# I2C_MUX.net
KiCad netlist of a schematic drawn in Altium Designer
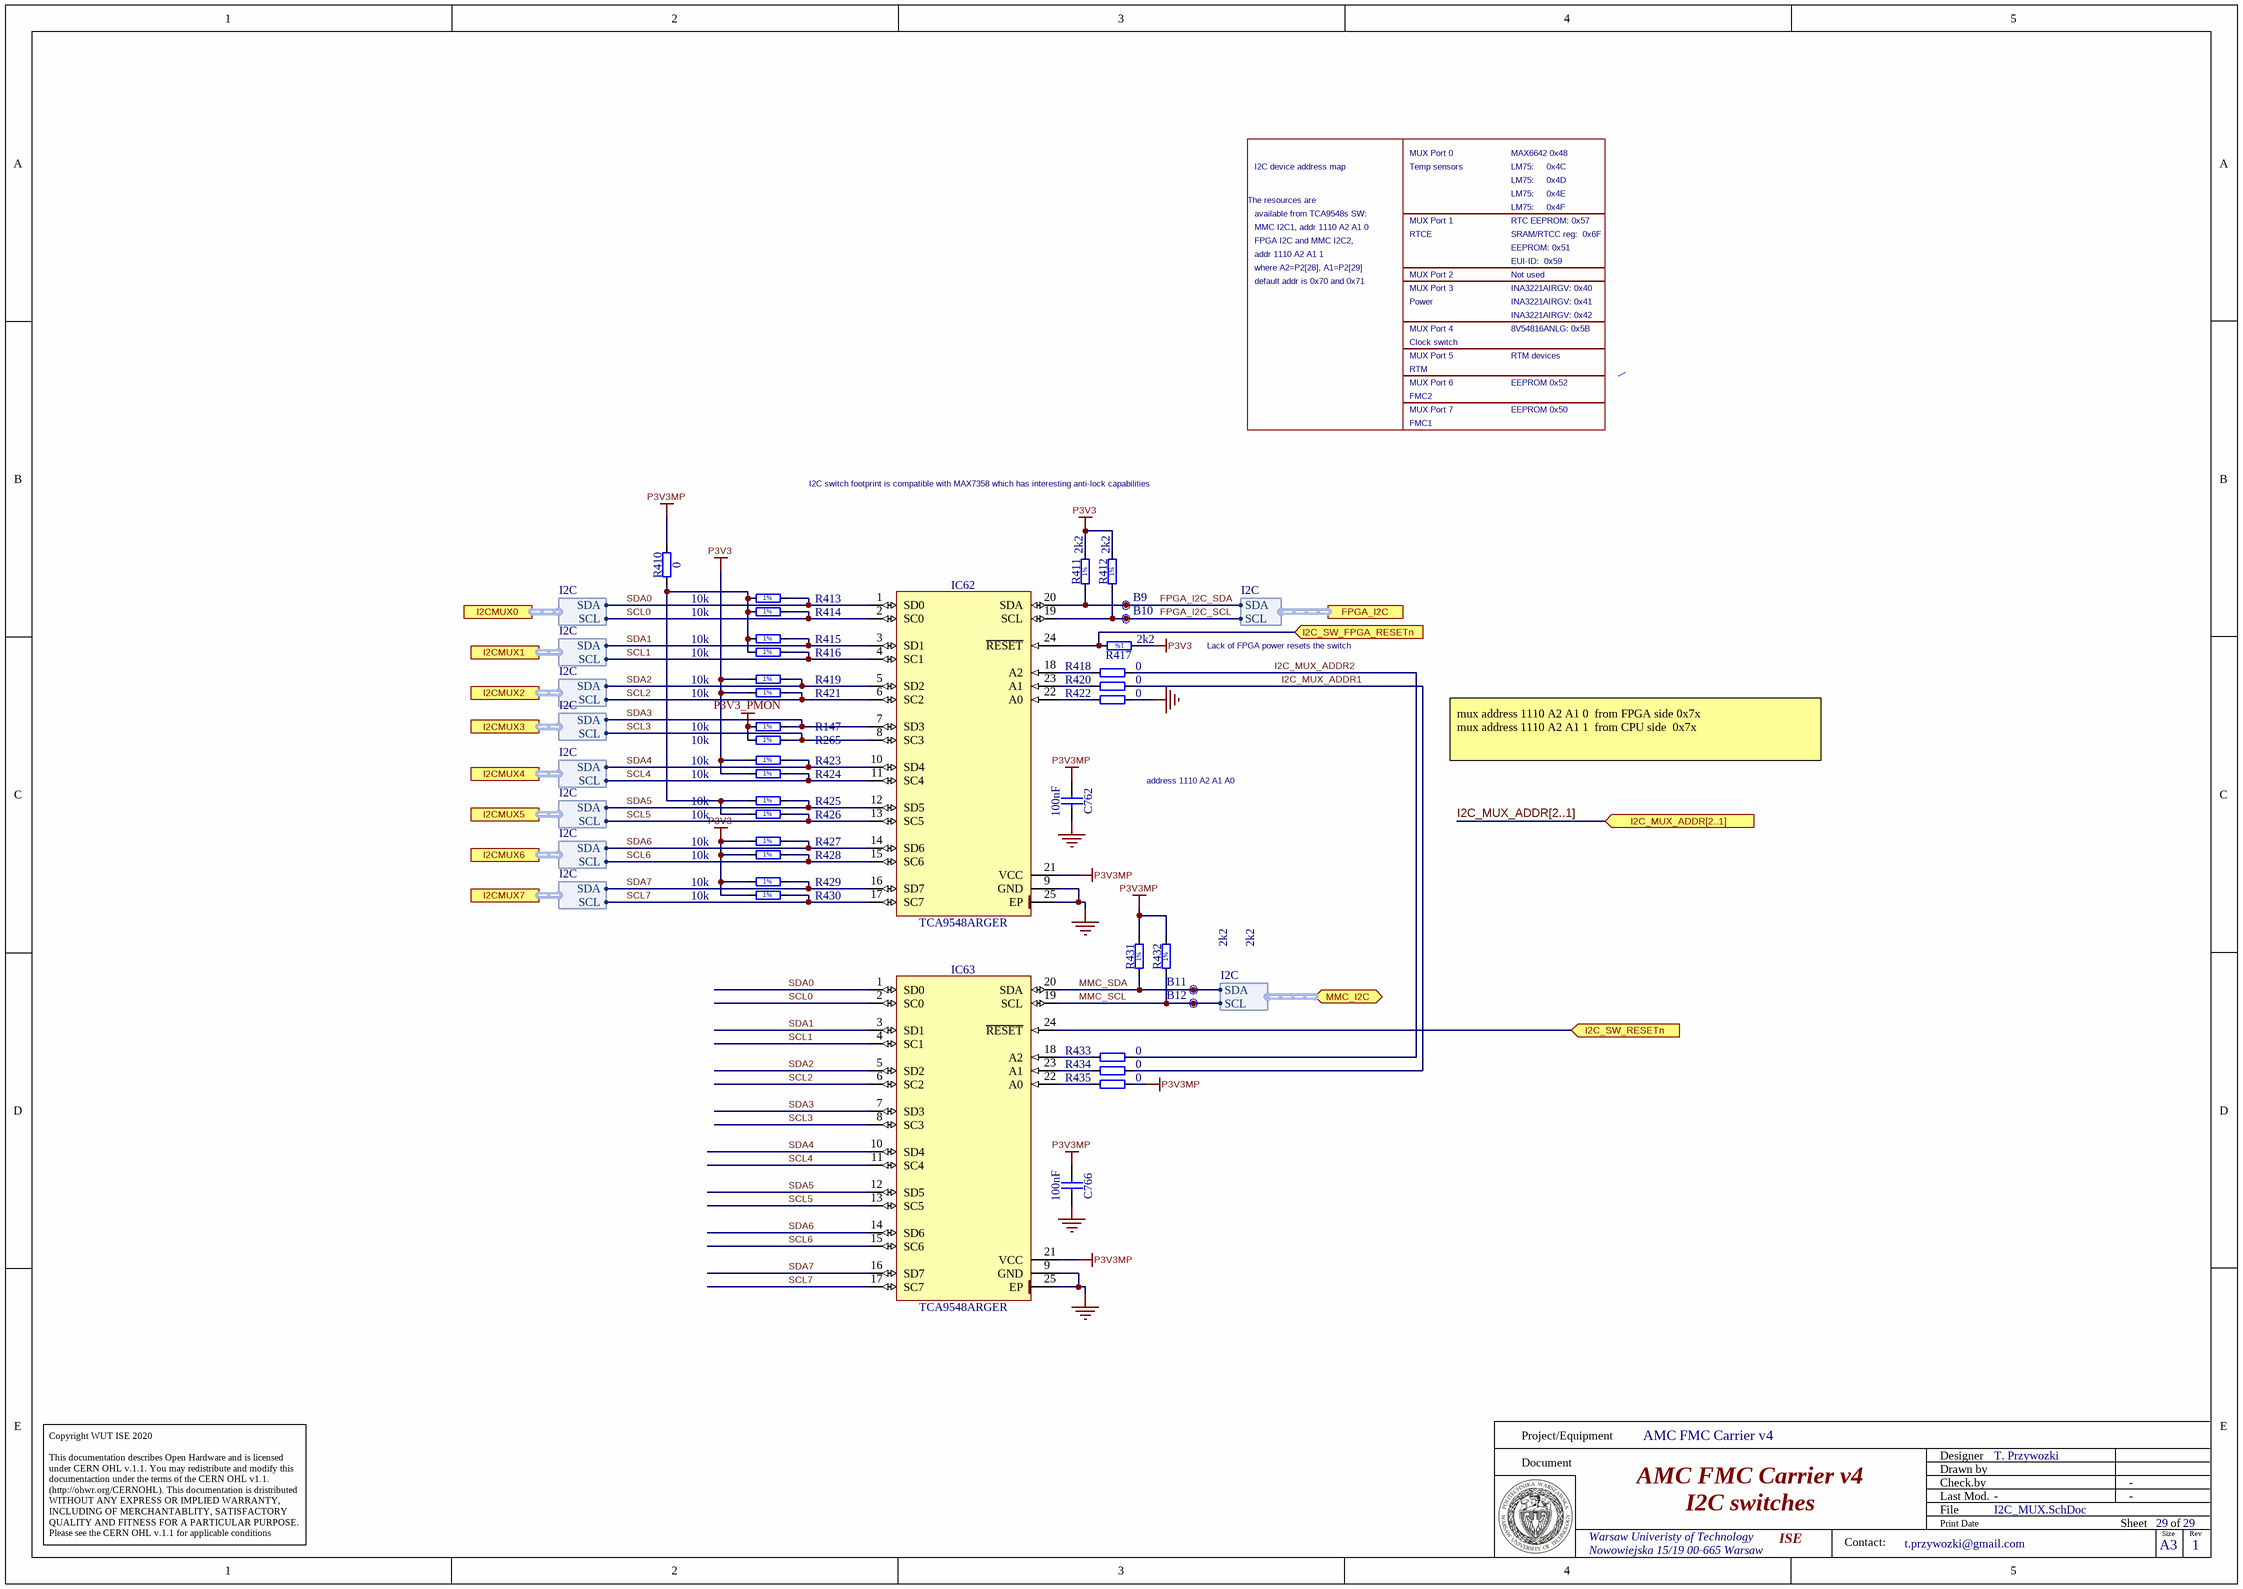
[diagram p0: I2C_MUX.SchDoc]

(export (version "E")
  (design (tool "Eeschema 10.0.6"))
  (components
    (comp (ref "B9")
      (value "SMD_PAD_D1MM")
      (footprint "C100")
      (libsource (lib "altium-import") (part "root_0__*"))
    )
    (comp (ref "B10")
      (value "SMD_PAD_D1MM")
      (footprint "C100")
      (libsource (lib "altium-import") (part "root_0__*"))
    )
    (comp (ref "B11")
      (value "SMD_PAD_D1MM")
      (footprint "C100")
      (libsource (lib "altium-import") (part "root_0__*"))
    )
    (comp (ref "B12")
      (value "SMD_PAD_D1MM")
      (footprint "C100")
      (libsource (lib "altium-import") (part "root_0__*"))
    )
    (comp (ref "C762")
      (value "100nF")
      (footprint "CAPC0603X33N")
      (description "Non-polarised capacitor")
      (fields
        (field (name "MANUFACTURER PART NUMBER") "CC0201_100NF_6.3V_10%_X5R")
        (field (name "MANUFACTURER") "GENERIC")
        (field (name "AUTHOR") "CERN DEM JLC")
      )
      (libsource (lib "Capacitors") (part "Capacitor - non polarized"))
    )
    (comp (ref "C766")
      (value "100nF")
      (footprint "CAPC0603X33N")
      (description "Non-polarised capacitor")
      (fields
        (field (name "MANUFACTURER PART NUMBER") "CC0201_100NF_6.3V_10%_X5R")
        (field (name "MANUFACTURER") "GENERIC")
        (field (name "AUTHOR") "CERN DEM JLC")
      )
      (libsource (lib "Capacitors") (part "Capacitor - non polarized"))
    )
    (comp (ref "IC62")
      (value "TCA9548ARGER")
      (footprint "QFN50P400X400X100-25N-S220")
      (description "Low Voltage 8-Channel I2C Switch With Reset")
      (fields (field (name "MANUFACTURER") "TEXAS INSTRUMENTS") (field (name "AUTHOR") "CERN DEM JLC"))
      (libsource (lib "ICs And Semiconductors") (part "TCA9548ARGER"))
    )
    (comp (ref "IC63")
      (value "TCA9548ARGER")
      (footprint "QFN50P400X400X100-25N-S220")
      (description "Low Voltage 8-Channel I2C Switch With Reset")
      (fields (field (name "MANUFACTURER") "TEXAS INSTRUMENTS") (field (name "AUTHOR") "CERN DEM JLC"))
      (libsource (lib "ICs And Semiconductors") (part "TCA9548ARGER"))
    )
    (comp (ref "R147")
      (value "10k")
      (footprint "RESC1005X40N")
      (description "Resistor - 1%")
      (fields
        (field (name "MANUFACTURER PART NUMBER") "R0402_10K_1%_0.0625W_100PPM")
        (field (name "MANUFACTURER") "GENERIC")
        (field (name "AUTHOR") "CERN DEM JLC")
      )
      (libsource (lib "Resistors") (part "Resistor - 1%"))
    )
    (comp (ref "R265")
      (value "10k")
      (footprint "RESC1005X40N")
      (description "Resistor - 1%")
      (fields
        (field (name "MANUFACTURER PART NUMBER") "R0402_10K_1%_0.0625W_100PPM")
        (field (name "MANUFACTURER") "GENERIC")
        (field (name "AUTHOR") "CERN DEM JLC")
      )
      (libsource (lib "Resistors") (part "Resistor - 1%"))
    )
    (comp (ref "R410")
      (value "0")
      (footprint "RESC1005X40N")
      (description "Resistor")
      (fields
        (field (name "MANUFACTURER PART NUMBER") "R0402_0R_JUMPER")
        (field (name "MANUFACTURER") "GENERIC")
        (field (name "AUTHOR") "CERN DEM JLC")
      )
      (libsource (lib "Resistors") (part "Resistor"))
    )
    (comp (ref "R411")
      (value "2k2")
      (footprint "RESC1005X40N")
      (description "Resistor - 1%")
      (fields
        (field (name "MANUFACTURER PART NUMBER") "R0402_2K2_1%_0.0625W_100PPM")
        (field (name "MANUFACTURER") "GENERIC")
        (field (name "AUTHOR") "CERN DEM JLC")
      )
      (libsource (lib "Resistors") (part "Resistor - 1%"))
    )
    (comp (ref "R412")
      (value "2k2")
      (footprint "RESC1005X40N")
      (description "Resistor - 1%")
      (fields
        (field (name "MANUFACTURER PART NUMBER") "R0402_2K2_1%_0.0625W_100PPM")
        (field (name "MANUFACTURER") "GENERIC")
        (field (name "AUTHOR") "CERN DEM JLC")
      )
      (libsource (lib "Resistors") (part "Resistor - 1%"))
    )
    (comp (ref "R413")
      (value "10k")
      (footprint "RESC1005X40N")
      (description "Resistor - 1%")
      (fields
        (field (name "MANUFACTURER PART NUMBER") "R0402_10K_1%_0.0625W_100PPM")
        (field (name "MANUFACTURER") "GENERIC")
        (field (name "AUTHOR") "CERN DEM JLC")
      )
      (libsource (lib "Resistors") (part "Resistor - 1%"))
    )
    (comp (ref "R414")
      (value "10k")
      (footprint "RESC1005X40N")
      (description "Resistor - 1%")
      (fields
        (field (name "MANUFACTURER PART NUMBER") "R0402_10K_1%_0.0625W_100PPM")
        (field (name "MANUFACTURER") "GENERIC")
        (field (name "AUTHOR") "CERN DEM JLC")
      )
      (libsource (lib "Resistors") (part "Resistor - 1%"))
    )
    (comp (ref "R415")
      (value "10k")
      (footprint "RESC1005X40N")
      (description "Resistor - 1%")
      (fields
        (field (name "MANUFACTURER PART NUMBER") "R0402_10K_1%_0.0625W_100PPM")
        (field (name "MANUFACTURER") "GENERIC")
        (field (name "AUTHOR") "CERN DEM JLC")
      )
      (libsource (lib "Resistors") (part "Resistor - 1%"))
    )
    (comp (ref "R416")
      (value "10k")
      (footprint "RESC1005X40N")
      (description "Resistor - 1%")
      (fields
        (field (name "MANUFACTURER PART NUMBER") "R0402_10K_1%_0.0625W_100PPM")
        (field (name "MANUFACTURER") "GENERIC")
        (field (name "AUTHOR") "CERN DEM JLC")
      )
      (libsource (lib "Resistors") (part "Resistor - 1%"))
    )
    (comp (ref "R417")
      (value "2k2")
      (footprint "RESC1005X40N")
      (description "Resistor - 1%")
      (fields
        (field (name "MANUFACTURER PART NUMBER") "R0402_2K2_1%_0.0625W_100PPM")
        (field (name "MANUFACTURER") "GENERIC")
        (field (name "AUTHOR") "CERN DEM JLC")
      )
      (libsource (lib "Resistors") (part "Resistor - 1%"))
    )
    (comp (ref "R418")
      (value "0")
      (footprint "RESC1005X40N")
      (description "Resistor")
      (fields
        (field (name "MANUFACTURER PART NUMBER") "R0402_0R_JUMPER")
        (field (name "MANUFACTURER") "GENERIC")
        (field (name "AUTHOR") "CERN DEM JLC")
      )
      (libsource (lib "Resistors") (part "Resistor"))
    )
    (comp (ref "R419")
      (value "10k")
      (footprint "RESC1005X40N")
      (description "Resistor - 1%")
      (fields
        (field (name "MANUFACTURER PART NUMBER") "R0402_10K_1%_0.0625W_100PPM")
        (field (name "MANUFACTURER") "GENERIC")
        (field (name "AUTHOR") "CERN DEM JLC")
      )
      (libsource (lib "Resistors") (part "Resistor - 1%"))
    )
    (comp (ref "R420")
      (value "0")
      (footprint "RESC1005X40N")
      (description "Resistor")
      (fields
        (field (name "MANUFACTURER PART NUMBER") "R0402_0R_JUMPER")
        (field (name "MANUFACTURER") "GENERIC")
        (field (name "AUTHOR") "CERN DEM JLC")
      )
      (libsource (lib "Resistors") (part "Resistor"))
    )
    (comp (ref "R421")
      (value "10k")
      (footprint "RESC1005X40N")
      (description "Resistor - 1%")
      (fields
        (field (name "MANUFACTURER PART NUMBER") "R0402_10K_1%_0.0625W_100PPM")
        (field (name "MANUFACTURER") "GENERIC")
        (field (name "AUTHOR") "CERN DEM JLC")
      )
      (libsource (lib "Resistors") (part "Resistor - 1%"))
    )
    (comp (ref "R422")
      (value "0")
      (footprint "RESC1005X40N")
      (description "Resistor")
      (fields
        (field (name "MANUFACTURER PART NUMBER") "R0402_0R_JUMPER")
        (field (name "MANUFACTURER") "GENERIC")
        (field (name "AUTHOR") "CERN DEM JLC")
      )
      (libsource (lib "Resistors") (part "Resistor"))
    )
    (comp (ref "R423")
      (value "10k")
      (footprint "RESC1005X40N")
      (description "Resistor - 1%")
      (fields
        (field (name "MANUFACTURER PART NUMBER") "R0402_10K_1%_0.0625W_100PPM")
        (field (name "MANUFACTURER") "GENERIC")
        (field (name "AUTHOR") "CERN DEM JLC")
      )
      (libsource (lib "Resistors") (part "Resistor - 1%"))
    )
    (comp (ref "R424")
      (value "10k")
      (footprint "RESC1005X40N")
      (description "Resistor - 1%")
      (fields
        (field (name "MANUFACTURER PART NUMBER") "R0402_10K_1%_0.0625W_100PPM")
        (field (name "MANUFACTURER") "GENERIC")
        (field (name "AUTHOR") "CERN DEM JLC")
      )
      (libsource (lib "Resistors") (part "Resistor - 1%"))
    )
    (comp (ref "R425")
      (value "10k")
      (footprint "RESC1005X40N")
      (description "Resistor - 1%")
      (fields
        (field (name "MANUFACTURER PART NUMBER") "R0402_10K_1%_0.0625W_100PPM")
        (field (name "MANUFACTURER") "GENERIC")
        (field (name "AUTHOR") "CERN DEM JLC")
      )
      (libsource (lib "Resistors") (part "Resistor - 1%"))
    )
    (comp (ref "R426")
      (value "10k")
      (footprint "RESC1005X40N")
      (description "Resistor - 1%")
      (fields
        (field (name "MANUFACTURER PART NUMBER") "R0402_10K_1%_0.0625W_100PPM")
        (field (name "MANUFACTURER") "GENERIC")
        (field (name "AUTHOR") "CERN DEM JLC")
      )
      (libsource (lib "Resistors") (part "Resistor - 1%"))
    )
    (comp (ref "R427")
      (value "10k")
      (footprint "RESC1005X40N")
      (description "Resistor - 1%")
      (fields
        (field (name "MANUFACTURER PART NUMBER") "R0402_10K_1%_0.0625W_100PPM")
        (field (name "MANUFACTURER") "GENERIC")
        (field (name "AUTHOR") "CERN DEM JLC")
      )
      (libsource (lib "Resistors") (part "Resistor - 1%"))
    )
    (comp (ref "R428")
      (value "10k")
      (footprint "RESC1005X40N")
      (description "Resistor - 1%")
      (fields
        (field (name "MANUFACTURER PART NUMBER") "R0402_10K_1%_0.0625W_100PPM")
        (field (name "MANUFACTURER") "GENERIC")
        (field (name "AUTHOR") "CERN DEM JLC")
      )
      (libsource (lib "Resistors") (part "Resistor - 1%"))
    )
    (comp (ref "R429")
      (value "10k")
      (footprint "RESC1005X40N")
      (description "Resistor - 1%")
      (fields
        (field (name "MANUFACTURER PART NUMBER") "R0402_10K_1%_0.0625W_100PPM")
        (field (name "MANUFACTURER") "GENERIC")
        (field (name "AUTHOR") "CERN DEM JLC")
      )
      (libsource (lib "Resistors") (part "Resistor - 1%"))
    )
    (comp (ref "R430")
      (value "10k")
      (footprint "RESC1005X40N")
      (description "Resistor - 1%")
      (fields
        (field (name "MANUFACTURER PART NUMBER") "R0402_10K_1%_0.0625W_100PPM")
        (field (name "MANUFACTURER") "GENERIC")
        (field (name "AUTHOR") "CERN DEM JLC")
      )
      (libsource (lib "Resistors") (part "Resistor - 1%"))
    )
    (comp (ref "R431")
      (value "2k2")
      (footprint "RESC1005X40N")
      (description "Resistor - 1%")
      (fields
        (field (name "MANUFACTURER PART NUMBER") "R0402_2K2_1%_0.0625W_100PPM")
        (field (name "MANUFACTURER") "GENERIC")
        (field (name "AUTHOR") "CERN DEM JLC")
      )
      (libsource (lib "Resistors") (part "Resistor - 1%"))
    )
    (comp (ref "R432")
      (value "2k2")
      (footprint "RESC1005X40N")
      (description "Resistor - 1%")
      (fields
        (field (name "MANUFACTURER PART NUMBER") "R0402_2K2_1%_0.0625W_100PPM")
        (field (name "MANUFACTURER") "GENERIC")
        (field (name "AUTHOR") "CERN DEM JLC")
      )
      (libsource (lib "Resistors") (part "Resistor - 1%"))
    )
    (comp (ref "R433")
      (value "0")
      (footprint "RESC1005X40N")
      (description "Resistor")
      (fields
        (field (name "MANUFACTURER PART NUMBER") "R0402_0R_JUMPER")
        (field (name "MANUFACTURER") "GENERIC")
        (field (name "AUTHOR") "CERN DEM JLC")
      )
      (libsource (lib "Resistors") (part "Resistor"))
    )
    (comp (ref "R434")
      (value "0")
      (footprint "RESC1005X40N")
      (description "Resistor")
      (fields
        (field (name "MANUFACTURER PART NUMBER") "R0402_0R_JUMPER")
        (field (name "MANUFACTURER") "GENERIC")
        (field (name "AUTHOR") "CERN DEM JLC")
      )
      (libsource (lib "Resistors") (part "Resistor"))
    )
    (comp (ref "R435")
      (value "0")
      (footprint "RESC1005X40N")
      (description "Resistor")
      (fields
        (field (name "MANUFACTURER PART NUMBER") "R0402_0R_JUMPER")
        (field (name "MANUFACTURER") "GENERIC")
        (field (name "AUTHOR") "CERN DEM JLC")
      )
      (libsource (lib "Resistors") (part "Resistor"))
    )
  )
  (nets
    (net (code "2") (name "/FPGA_I2C_SCL") (class "Default")
      (node (ref "B10") (pin "1") (pinfunction "1_1") (pintype "passive"))
      (node (ref "IC62") (pin "19") (pinfunction "SCL_19") (pintype "bidirectional"))
      (node (ref "R412") (pin "1") (pinfunction "1_1") (pintype "passive"))
    )
    (net (code "3") (name "/FPGA_I2C_SDA") (class "Default")
      (node (ref "B9") (pin "1") (pinfunction "1_1") (pintype "passive"))
      (node (ref "IC62") (pin "20") (pinfunction "SDA_20") (pintype "bidirectional"))
      (node (ref "R411") (pin "1") (pinfunction "1_1") (pintype "passive"))
    )
    (net (code "4") (name "/I2C_MUX_ADDR1") (class "Default")
      (node (ref "R420") (pin "1") (pinfunction "1_1") (pintype "passive"))
      (node (ref "R434") (pin "1") (pinfunction "1_1") (pintype "passive"))
    )
    (net (code "5") (name "/I2C_MUX_ADDR2") (class "Default")
      (node (ref "R418") (pin "1") (pinfunction "1_1") (pintype "passive"))
      (node (ref "R433") (pin "1") (pinfunction "1_1") (pintype "passive"))
    )
    (net (code "7") (name "/I2C_SW_FPGA_RESETn") (class "Default")
      (node (ref "IC62") (pin "24") (pinfunction "~{RESET}_24") (pintype "input"))
      (node (ref "R417") (pin "2") (pinfunction "2_2") (pintype "passive"))
    )
    (net (code "8") (name "/I2C_SW_RESETn") (class "Default")
      (node (ref "IC63") (pin "24") (pinfunction "~{RESET}_24") (pintype "input"))
    )
    (net (code "9") (name "/MMC_SCL") (class "Default")
      (node (ref "B12") (pin "1") (pinfunction "1_1") (pintype "passive"))
      (node (ref "IC63") (pin "19") (pinfunction "SCL_19") (pintype "bidirectional"))
      (node (ref "R432") (pin "1") (pinfunction "1_1") (pintype "passive"))
    )
    (net (code "10") (name "/MMC_SDA") (class "Default")
      (node (ref "B11") (pin "1") (pinfunction "1_1") (pintype "passive"))
      (node (ref "IC63") (pin "20") (pinfunction "SDA_20") (pintype "bidirectional"))
      (node (ref "R431") (pin "1") (pinfunction "1_1") (pintype "passive"))
    )
    (net (code "11") (name "/SCL0") (class "Default")
      (node (ref "IC62") (pin "2") (pinfunction "SC0_2") (pintype "bidirectional"))
      (node (ref "IC63") (pin "2") (pinfunction "SC0_2") (pintype "bidirectional"))
      (node (ref "R414") (pin "2") (pinfunction "2_2") (pintype "passive"))
    )
    (net (code "12") (name "/SCL1") (class "Default")
      (node (ref "IC62") (pin "4") (pinfunction "SC1_4") (pintype "bidirectional"))
      (node (ref "IC63") (pin "4") (pinfunction "SC1_4") (pintype "bidirectional"))
      (node (ref "R416") (pin "2") (pinfunction "2_2") (pintype "passive"))
    )
    (net (code "13") (name "/SCL2") (class "Default")
      (node (ref "IC62") (pin "6") (pinfunction "SC2_6") (pintype "bidirectional"))
      (node (ref "IC63") (pin "6") (pinfunction "SC2_6") (pintype "bidirectional"))
      (node (ref "R421") (pin "2") (pinfunction "2_2") (pintype "passive"))
    )
    (net (code "14") (name "/SCL3") (class "Default")
      (node (ref "IC62") (pin "8") (pinfunction "SC3_8") (pintype "bidirectional"))
      (node (ref "IC63") (pin "8") (pinfunction "SC3_8") (pintype "bidirectional"))
      (node (ref "R265") (pin "2") (pinfunction "2_2") (pintype "passive"))
    )
    (net (code "15") (name "/SCL4") (class "Default")
      (node (ref "IC62") (pin "11") (pinfunction "SC4_11") (pintype "bidirectional"))
      (node (ref "IC63") (pin "11") (pinfunction "SC4_11") (pintype "bidirectional"))
      (node (ref "R424") (pin "2") (pinfunction "2_2") (pintype "passive"))
    )
    (net (code "16") (name "/SCL5") (class "Default")
      (node (ref "IC62") (pin "13") (pinfunction "SC5_13") (pintype "bidirectional"))
      (node (ref "IC63") (pin "13") (pinfunction "SC5_13") (pintype "bidirectional"))
      (node (ref "R426") (pin "2") (pinfunction "2_2") (pintype "passive"))
    )
    (net (code "17") (name "/SCL6") (class "Default")
      (node (ref "IC62") (pin "15") (pinfunction "SC6_15") (pintype "bidirectional"))
      (node (ref "IC63") (pin "15") (pinfunction "SC6_15") (pintype "bidirectional"))
      (node (ref "R428") (pin "2") (pinfunction "2_2") (pintype "passive"))
    )
    (net (code "18") (name "/SCL7") (class "Default")
      (node (ref "IC62") (pin "17") (pinfunction "SC7_17") (pintype "bidirectional"))
      (node (ref "IC63") (pin "17") (pinfunction "SC7_17") (pintype "bidirectional"))
      (node (ref "R430") (pin "2") (pinfunction "2_2") (pintype "passive"))
    )
    (net (code "19") (name "/SDA0") (class "Default")
      (node (ref "IC62") (pin "1") (pinfunction "SD0_1") (pintype "bidirectional"))
      (node (ref "IC63") (pin "1") (pinfunction "SD0_1") (pintype "bidirectional"))
      (node (ref "R413") (pin "2") (pinfunction "2_2") (pintype "passive"))
    )
    (net (code "20") (name "/SDA1") (class "Default")
      (node (ref "IC62") (pin "3") (pinfunction "SD1_3") (pintype "bidirectional"))
      (node (ref "IC63") (pin "3") (pinfunction "SD1_3") (pintype "bidirectional"))
      (node (ref "R415") (pin "2") (pinfunction "2_2") (pintype "passive"))
    )
    (net (code "21") (name "/SDA2") (class "Default")
      (node (ref "IC62") (pin "5") (pinfunction "SD2_5") (pintype "bidirectional"))
      (node (ref "IC63") (pin "5") (pinfunction "SD2_5") (pintype "bidirectional"))
      (node (ref "R419") (pin "2") (pinfunction "2_2") (pintype "passive"))
    )
    (net (code "22") (name "/SDA3") (class "Default")
      (node (ref "IC62") (pin "7") (pinfunction "SD3_7") (pintype "bidirectional"))
      (node (ref "IC63") (pin "7") (pinfunction "SD3_7") (pintype "bidirectional"))
      (node (ref "R147") (pin "2") (pinfunction "2_2") (pintype "passive"))
    )
    (net (code "23") (name "/SDA4") (class "Default")
      (node (ref "IC62") (pin "10") (pinfunction "SD4_10") (pintype "bidirectional"))
      (node (ref "IC63") (pin "10") (pinfunction "SD4_10") (pintype "bidirectional"))
      (node (ref "R423") (pin "2") (pinfunction "2_2") (pintype "passive"))
    )
    (net (code "24") (name "/SDA5") (class "Default")
      (node (ref "IC62") (pin "12") (pinfunction "SD5_12") (pintype "bidirectional"))
      (node (ref "IC63") (pin "12") (pinfunction "SD5_12") (pintype "bidirectional"))
      (node (ref "R425") (pin "2") (pinfunction "2_2") (pintype "passive"))
    )
    (net (code "25") (name "/SDA6") (class "Default")
      (node (ref "IC62") (pin "14") (pinfunction "SD6_14") (pintype "bidirectional"))
      (node (ref "IC63") (pin "14") (pinfunction "SD6_14") (pintype "bidirectional"))
      (node (ref "R427") (pin "2") (pinfunction "2_2") (pintype "passive"))
    )
    (net (code "26") (name "/SDA7") (class "Default")
      (node (ref "IC62") (pin "16") (pinfunction "SD7_16") (pintype "bidirectional"))
      (node (ref "IC63") (pin "16") (pinfunction "SD7_16") (pintype "bidirectional"))
      (node (ref "R429") (pin "2") (pinfunction "2_2") (pintype "passive"))
    )
    (net (code "28") (name "GND") (class "Default")
      (node (ref "C762") (pin "2") (pinfunction "2_2") (pintype "passive"))
      (node (ref "C766") (pin "2") (pinfunction "2_2") (pintype "passive"))
      (node (ref "IC62") (pin "25") (pinfunction "EP_25") (pintype "power_in"))
      (node (ref "IC62") (pin "9") (pinfunction "GND_9") (pintype "power_in"))
      (node (ref "IC63") (pin "25") (pinfunction "EP_25") (pintype "power_in"))
      (node (ref "IC63") (pin "9") (pinfunction "GND_9") (pintype "power_in"))
      (node (ref "R422") (pin "1") (pinfunction "1_1") (pintype "passive"))
    )
    (net (code "29") (name "Net-(IC62-A0)") (class "Default")
      (node (ref "IC62") (pin "22") (pinfunction "A0_22") (pintype "input"))
      (node (ref "R422") (pin "2") (pinfunction "2_2") (pintype "passive"))
    )
    (net (code "30") (name "Net-(IC62-A1)") (class "Default")
      (node (ref "IC62") (pin "23") (pinfunction "A1_23") (pintype "input"))
      (node (ref "R420") (pin "2") (pinfunction "2_2") (pintype "passive"))
    )
    (net (code "31") (name "Net-(IC62-A2)") (class "Default")
      (node (ref "IC62") (pin "18") (pinfunction "A2_18") (pintype "input"))
      (node (ref "R418") (pin "2") (pinfunction "2_2") (pintype "passive"))
    )
    (net (code "32") (name "Net-(IC63-A0)") (class "Default")
      (node (ref "IC63") (pin "22") (pinfunction "A0_22") (pintype "input"))
      (node (ref "R435") (pin "2") (pinfunction "2_2") (pintype "passive"))
    )
    (net (code "33") (name "Net-(IC63-A1)") (class "Default")
      (node (ref "IC63") (pin "23") (pinfunction "A1_23") (pintype "input"))
      (node (ref "R434") (pin "2") (pinfunction "2_2") (pintype "passive"))
    )
    (net (code "34") (name "Net-(IC63-A2)") (class "Default")
      (node (ref "IC63") (pin "18") (pinfunction "A2_18") (pintype "input"))
      (node (ref "R433") (pin "2") (pinfunction "2_2") (pintype "passive"))
    )
    (net (code "35") (name "Net-(R410-Pad2)") (class "Default")
      (node (ref "R410") (pin "2") (pinfunction "2_2") (pintype "passive"))
      (node (ref "R413") (pin "1") (pinfunction "1_1") (pintype "passive"))
      (node (ref "R414") (pin "1") (pinfunction "1_1") (pintype "passive"))
      (node (ref "R415") (pin "1") (pinfunction "1_1") (pintype "passive"))
      (node (ref "R416") (pin "1") (pinfunction "1_1") (pintype "passive"))
      (node (ref "R425") (pin "1") (pinfunction "1_1") (pintype "passive"))
      (node (ref "R426") (pin "1") (pinfunction "1_1") (pintype "passive"))
    )
    (net (code "36") (name "P3V3") (class "Default")
      (node (ref "R411") (pin "2") (pinfunction "2_2") (pintype "passive"))
      (node (ref "R412") (pin "2") (pinfunction "2_2") (pintype "passive"))
      (node (ref "R417") (pin "1") (pinfunction "1_1") (pintype "passive"))
      (node (ref "R419") (pin "1") (pinfunction "1_1") (pintype "passive"))
      (node (ref "R421") (pin "1") (pinfunction "1_1") (pintype "passive"))
      (node (ref "R423") (pin "1") (pinfunction "1_1") (pintype "passive"))
      (node (ref "R424") (pin "1") (pinfunction "1_1") (pintype "passive"))
      (node (ref "R427") (pin "1") (pinfunction "1_1") (pintype "passive"))
      (node (ref "R428") (pin "1") (pinfunction "1_1") (pintype "passive"))
      (node (ref "R429") (pin "1") (pinfunction "1_1") (pintype "passive"))
      (node (ref "R430") (pin "1") (pinfunction "1_1") (pintype "passive"))
    )
    (net (code "37") (name "P3V3MP") (class "Default")
      (node (ref "C762") (pin "1") (pinfunction "1_1") (pintype "passive"))
      (node (ref "C766") (pin "1") (pinfunction "1_1") (pintype "passive"))
      (node (ref "IC62") (pin "21") (pinfunction "VCC_21") (pintype "power_in"))
      (node (ref "IC63") (pin "21") (pinfunction "VCC_21") (pintype "power_in"))
      (node (ref "R410") (pin "1") (pinfunction "1_1") (pintype "passive"))
      (node (ref "R431") (pin "2") (pinfunction "2_2") (pintype "passive"))
      (node (ref "R432") (pin "2") (pinfunction "2_2") (pintype "passive"))
      (node (ref "R435") (pin "1") (pinfunction "1_1") (pintype "passive"))
    )
    (net (code "38") (name "P3V3_PMON") (class "Default")
      (node (ref "R147") (pin "1") (pinfunction "1_1") (pintype "passive"))
      (node (ref "R265") (pin "1") (pinfunction "1_1") (pintype "passive"))
    )
  )
)
